# DRV8711_Breakout_Minimal.net
KiCad netlist of a schematic drawn in EAGLE
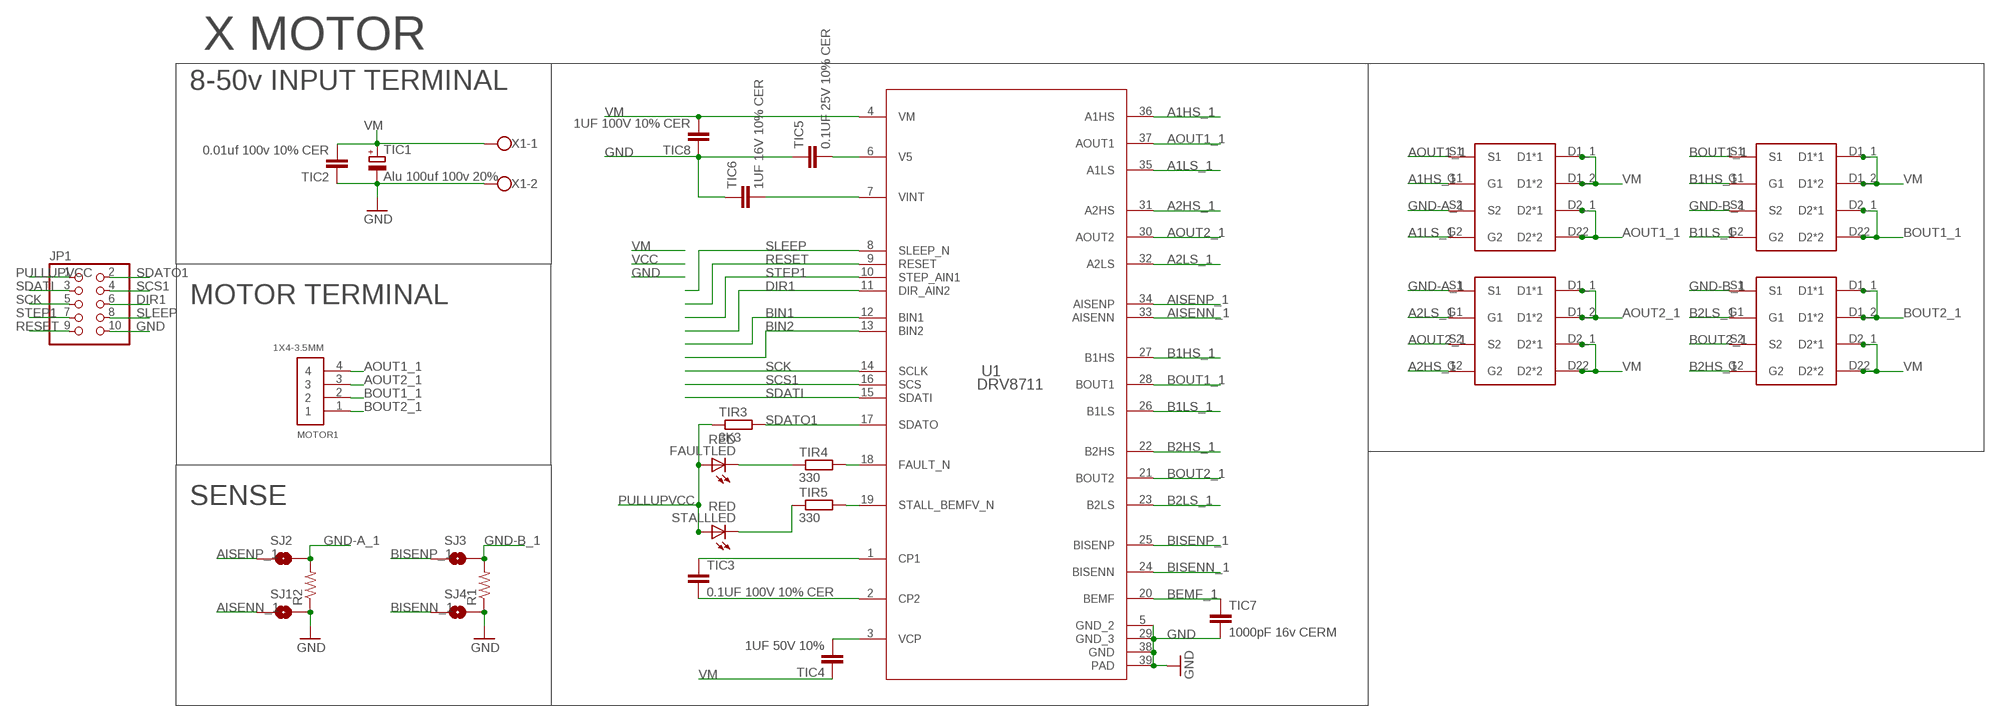
[diagram p0: schematic, sheet 1]

(export (version "E")
  (design (tool "Eeschema 10.0.6"))
  (components
    (comp (ref "FAULTLED")
      (value "RED")
      (footprint "eagle-import:1206")
      (libsource (lib "eagle-import") (part "LEDSMT1206"))
    )
    (comp (ref "JP1")
      (value "PINHD-2X5")
      (footprint "eagle-import:2X05")
      (libsource (lib "eagle-import") (part "PINHD-2X5"))
    )
    (comp (ref "MOTOR1")
      (value "1X4-3.5MM")
      (footprint "eagle-import:1X04-3.5MM")
      (libsource (lib "eagle-import") (part "1X4-3.5MM"))
    )
    (comp (ref "R1")
      (value "R-US_R2512")
      (footprint "eagle-import:R2512")
      (libsource (lib "eagle-import") (part "R-US_R2512"))
    )
    (comp (ref "R2")
      (value "R-US_R2512")
      (footprint "eagle-import:R2512")
      (libsource (lib "eagle-import") (part "R-US_R2512"))
    )
    (comp (ref "SJ1")
      (value "SOLDERJUMPERTRACE")
      (footprint "eagle-import:SJ_2S-TRACE")
      (libsource (lib "eagle-import") (part "SOLDERJUMPERTRACE"))
    )
    (comp (ref "SJ2")
      (value "SOLDERJUMPERTRACE")
      (footprint "eagle-import:SJ_2S-TRACE")
      (libsource (lib "eagle-import") (part "SOLDERJUMPERTRACE"))
    )
    (comp (ref "SJ3")
      (value "SOLDERJUMPERTRACE")
      (footprint "eagle-import:SJ_2S-TRACE")
      (libsource (lib "eagle-import") (part "SOLDERJUMPERTRACE"))
    )
    (comp (ref "SJ4")
      (value "SOLDERJUMPERTRACE")
      (footprint "eagle-import:SJ_2S-TRACE")
      (libsource (lib "eagle-import") (part "SOLDERJUMPERTRACE"))
    )
    (comp (ref "STALLLED")
      (value "RED")
      (footprint "eagle-import:1206")
      (libsource (lib "eagle-import") (part "LEDSMT1206"))
    )
    (comp (ref "TIC1")
      (value "Alu 100uf 100v 20%")
      (footprint "eagle-import:PANASONIC_E")
      (libsource (lib "eagle-import") (part "CPOL-EUE"))
    )
    (comp (ref "TIC2")
      (value "0.01uf 100v 10% CER")
      (footprint "eagle-import:C1206K")
      (libsource (lib "eagle-import") (part "C-EUC1206K"))
    )
    (comp (ref "TIC3")
      (value "0.1UF 100V 10% CER")
      (footprint "eagle-import:C1206K")
      (libsource (lib "eagle-import") (part "C-EUC1206K"))
    )
    (comp (ref "TIC4")
      (value "1UF 50V 10%")
      (footprint "eagle-import:C1206K")
      (libsource (lib "eagle-import") (part "C-EUC1206K"))
    )
    (comp (ref "TIC5")
      (value "0.1UF 25V 10% CER")
      (footprint "eagle-import:C1206K")
      (libsource (lib "eagle-import") (part "C-EUC1206K"))
    )
    (comp (ref "TIC6")
      (value "1UF 16V 10% CER")
      (footprint "eagle-import:C1206K")
      (libsource (lib "eagle-import") (part "C-EUC1206K"))
    )
    (comp (ref "TIC7")
      (value "1000pF 16v CERM")
      (footprint "eagle-import:C1206K")
      (libsource (lib "eagle-import") (part "C-EUC1206K"))
    )
    (comp (ref "TIC8")
      (value "1UF 100V 10% CER")
      (footprint "eagle-import:C1206K")
      (libsource (lib "eagle-import") (part "C-EUC1206K"))
    )
    (comp (ref "TIR3")
      (value "3K3")
      (footprint "eagle-import:R1206")
      (libsource (lib "eagle-import") (part "R-EU_R1206"))
    )
    (comp (ref "TIR4")
      (value "330")
      (footprint "eagle-import:R1206")
      (libsource (lib "eagle-import") (part "R-EU_R1206"))
    )
    (comp (ref "TIR5")
      (value "330")
      (footprint "eagle-import:R1206")
      (libsource (lib "eagle-import") (part "R-EU_R1206"))
    )
    (comp (ref "U$1")
      (value "CSD88537ND")
      (footprint "eagle-import:CSD88537ND")
      (libsource (lib "eagle-import") (part "CSD88537ND"))
    )
    (comp (ref "U$2")
      (value "CSD88537ND")
      (footprint "eagle-import:CSD88537ND")
      (libsource (lib "eagle-import") (part "CSD88537ND"))
    )
    (comp (ref "U$3")
      (value "CSD88537ND")
      (footprint "eagle-import:CSD88537ND")
      (libsource (lib "eagle-import") (part "CSD88537ND"))
    )
    (comp (ref "U$4")
      (value "CSD88537ND")
      (footprint "eagle-import:CSD88537ND")
      (libsource (lib "eagle-import") (part "CSD88537ND"))
    )
    (comp (ref "U1")
      (value "DRV8711")
      (footprint "eagle-import:DCP0038A_N")
      (fields
        (field (name "ALTERNATEPARTNUMBER") "DRV8711DCP")
        (field (name "MANUFACTURER") "Texas Instruments")
        (field (name "PARTNUMBER") "DRV8711DCPR")
      )
      (libsource (lib "eagle-import") (part "DRV8711DCPR"))
    )
    (comp (ref "X1")
      (value "W237-102")
      (footprint "eagle-import:W237-102")
      (fields (field (name "MPN") "237-102"))
      (libsource (lib "eagle-import") (part "W237-102"))
    )
  )
  (nets
    (net (code "1") (name "/A1HS_1") (class "Default")
      (node (ref "U$1") (pin "G1") (pinfunction "G1_G1") (pintype "power_in"))
      (node (ref "U1") (pin "36") (pinfunction "A1HS_36") (pintype "output"))
    )
    (net (code "2") (name "/A1LS_1") (class "Default")
      (node (ref "U$1") (pin "G2") (pinfunction "G2_G2") (pintype "power_in"))
      (node (ref "U1") (pin "35") (pinfunction "A1LS_35") (pintype "output"))
    )
    (net (code "3") (name "/A2HS_1") (class "Default")
      (node (ref "U$3") (pin "G2") (pinfunction "G2_G2") (pintype "power_in"))
      (node (ref "U1") (pin "31") (pinfunction "A2HS_31") (pintype "output"))
    )
    (net (code "4") (name "/A2LS_1") (class "Default")
      (node (ref "U$3") (pin "G1") (pinfunction "G1_G1") (pintype "power_in"))
      (node (ref "U1") (pin "32") (pinfunction "A2LS_32") (pintype "output"))
    )
    (net (code "5") (name "/AISENN_1") (class "Default")
      (node (ref "SJ1") (pin "1") (pinfunction "1_1") (pintype "passive"))
      (node (ref "U1") (pin "33") (pinfunction "AISENN_33") (pintype "input"))
    )
    (net (code "6") (name "/AISENP_1") (class "Default")
      (node (ref "SJ2") (pin "1") (pinfunction "1_1") (pintype "passive"))
      (node (ref "U1") (pin "34") (pinfunction "AISENP_34") (pintype "input"))
    )
    (net (code "7") (name "/AOUT1_1") (class "Default")
      (node (ref "MOTOR1") (pin "4") (pinfunction "4_4") (pintype "bidirectional"))
      (node (ref "U$1") (pin "D22") (pinfunction "D2*2_D22") (pintype "power_in"))
      (node (ref "U$1") (pin "D2_1") (pinfunction "D2*1_D2_1") (pintype "power_in"))
      (node (ref "U$1") (pin "S1") (pinfunction "S1_S1") (pintype "power_in"))
      (node (ref "U1") (pin "37") (pinfunction "AOUT1_37") (pintype "output"))
    )
    (net (code "8") (name "/AOUT2_1") (class "Default")
      (node (ref "MOTOR1") (pin "3") (pinfunction "3_3") (pintype "bidirectional"))
      (node (ref "U$3") (pin "D1_1") (pinfunction "D1*1_D1_1") (pintype "power_in"))
      (node (ref "U$3") (pin "D1_2") (pinfunction "D1*2_D1_2") (pintype "power_in"))
      (node (ref "U$3") (pin "S2") (pinfunction "S2_S2") (pintype "power_in"))
      (node (ref "U1") (pin "30") (pinfunction "AOUT2_30") (pintype "output"))
    )
    (net (code "9") (name "/B1HS_1") (class "Default")
      (node (ref "U$2") (pin "G1") (pinfunction "G1_G1") (pintype "power_in"))
      (node (ref "U1") (pin "27") (pinfunction "B1HS_27") (pintype "output"))
    )
    (net (code "10") (name "/B1LS_1") (class "Default")
      (node (ref "U$2") (pin "G2") (pinfunction "G2_G2") (pintype "power_in"))
      (node (ref "U1") (pin "26") (pinfunction "B1LS_26") (pintype "output"))
    )
    (net (code "11") (name "/B2HS_1") (class "Default")
      (node (ref "U$4") (pin "G2") (pinfunction "G2_G2") (pintype "power_in"))
      (node (ref "U1") (pin "22") (pinfunction "B2HS_22") (pintype "output"))
    )
    (net (code "12") (name "/B2LS_1") (class "Default")
      (node (ref "U$4") (pin "G1") (pinfunction "G1_G1") (pintype "power_in"))
      (node (ref "U1") (pin "23") (pinfunction "B2LS_23") (pintype "output"))
    )
    (net (code "13") (name "/BEMF_1") (class "Default")
      (node (ref "TIC7") (pin "1") (pinfunction "1_1") (pintype "passive"))
      (node (ref "U1") (pin "20") (pinfunction "BEMF_20") (pintype "output"))
    )
    (net (code "14") (name "/BIN1") (class "Default")
      (node (ref "U1") (pin "12") (pinfunction "BIN1_12") (pintype "input"))
    )
    (net (code "15") (name "/BIN2") (class "Default")
      (node (ref "U1") (pin "13") (pinfunction "BIN2_13") (pintype "input"))
    )
    (net (code "16") (name "/BISENN_1") (class "Default")
      (node (ref "SJ4") (pin "1") (pinfunction "1_1") (pintype "passive"))
      (node (ref "U1") (pin "24") (pinfunction "BISENN_24") (pintype "input"))
    )
    (net (code "17") (name "/BISENP_1") (class "Default")
      (node (ref "SJ3") (pin "1") (pinfunction "1_1") (pintype "passive"))
      (node (ref "U1") (pin "25") (pinfunction "BISENP_25") (pintype "input"))
    )
    (net (code "18") (name "/BOUT1_1") (class "Default")
      (node (ref "MOTOR1") (pin "2") (pinfunction "2_2") (pintype "bidirectional"))
      (node (ref "U$2") (pin "D22") (pinfunction "D2*2_D22") (pintype "power_in"))
      (node (ref "U$2") (pin "D2_1") (pinfunction "D2*1_D2_1") (pintype "power_in"))
      (node (ref "U$2") (pin "S1") (pinfunction "S1_S1") (pintype "power_in"))
      (node (ref "U1") (pin "28") (pinfunction "BOUT1_28") (pintype "output"))
    )
    (net (code "19") (name "/BOUT2_1") (class "Default")
      (node (ref "MOTOR1") (pin "1") (pinfunction "1_1") (pintype "bidirectional"))
      (node (ref "U$4") (pin "D1_1") (pinfunction "D1*1_D1_1") (pintype "power_in"))
      (node (ref "U$4") (pin "D1_2") (pinfunction "D1*2_D1_2") (pintype "power_in"))
      (node (ref "U$4") (pin "S2") (pinfunction "S2_S2") (pintype "power_in"))
      (node (ref "U1") (pin "21") (pinfunction "BOUT2_21") (pintype "output"))
    )
    (net (code "20") (name "/DIR1") (class "Default")
      (node (ref "JP1") (pin "6") (pinfunction "6_6") (pintype "passive"))
      (node (ref "U1") (pin "11") (pinfunction "DIR_AIN2_11") (pintype "input"))
    )
    (net (code "21") (name "/GND-A_1") (class "Default")
      (node (ref "R2") (pin "2") (pinfunction "2_2") (pintype "passive"))
      (node (ref "SJ2") (pin "2") (pinfunction "2_2") (pintype "passive"))
      (node (ref "U$1") (pin "S2") (pinfunction "S2_S2") (pintype "power_in"))
      (node (ref "U$3") (pin "S1") (pinfunction "S1_S1") (pintype "power_in"))
    )
    (net (code "22") (name "/GND-B_1") (class "Default")
      (node (ref "R1") (pin "2") (pinfunction "2_2") (pintype "passive"))
      (node (ref "SJ3") (pin "2") (pinfunction "2_2") (pintype "passive"))
      (node (ref "U$2") (pin "S2") (pinfunction "S2_S2") (pintype "power_in"))
      (node (ref "U$4") (pin "S1") (pinfunction "S1_S1") (pintype "power_in"))
    )
    (net (code "23") (name "/PULLUPVCC") (class "Default")
      (node (ref "FAULTLED") (pin "A") (pinfunction "A_A") (pintype "passive"))
      (node (ref "JP1") (pin "1") (pinfunction "1_1") (pintype "passive"))
      (node (ref "STALLLED") (pin "A") (pinfunction "A_A") (pintype "passive"))
      (node (ref "TIR3") (pin "1") (pinfunction "1_1") (pintype "passive"))
    )
    (net (code "24") (name "/RESET") (class "Default")
      (node (ref "JP1") (pin "9") (pinfunction "9_9") (pintype "passive"))
      (node (ref "U1") (pin "9") (pinfunction "RESET_9") (pintype "input"))
    )
    (net (code "25") (name "/SCK") (class "Default")
      (node (ref "JP1") (pin "5") (pinfunction "5_5") (pintype "passive"))
      (node (ref "U1") (pin "14") (pinfunction "SCLK_14") (pintype "input"))
    )
    (net (code "26") (name "/SCS1") (class "Default")
      (node (ref "JP1") (pin "4") (pinfunction "4_4") (pintype "passive"))
      (node (ref "U1") (pin "16") (pinfunction "SCS_16") (pintype "input"))
    )
    (net (code "27") (name "/SDATI") (class "Default")
      (node (ref "JP1") (pin "3") (pinfunction "3_3") (pintype "passive"))
      (node (ref "U1") (pin "15") (pinfunction "SDATI_15") (pintype "input"))
    )
    (net (code "28") (name "/SDATO1") (class "Default")
      (node (ref "JP1") (pin "2") (pinfunction "2_2") (pintype "passive"))
      (node (ref "TIR3") (pin "2") (pinfunction "2_2") (pintype "passive"))
      (node (ref "U1") (pin "17") (pinfunction "SDATO_17") (pintype "open_collector"))
    )
    (net (code "29") (name "/SLEEP") (class "Default")
      (node (ref "JP1") (pin "8") (pinfunction "8_8") (pintype "passive"))
      (node (ref "U1") (pin "8") (pinfunction "SLEEP_N_8") (pintype "input"))
    )
    (net (code "30") (name "/STEP1") (class "Default")
      (node (ref "JP1") (pin "7") (pinfunction "7_7") (pintype "passive"))
      (node (ref "U1") (pin "10") (pinfunction "STEP_AIN1_10") (pintype "input"))
    )
    (net (code "32") (name "/VM") (class "Default")
      (node (ref "TIC1") (pin "+") (pinfunction "+_+") (pintype "passive"))
      (node (ref "TIC2") (pin "2") (pinfunction "2_2") (pintype "passive"))
      (node (ref "TIC4") (pin "1") (pinfunction "1_1") (pintype "passive"))
      (node (ref "TIC8") (pin "2") (pinfunction "2_2") (pintype "passive"))
      (node (ref "U$1") (pin "D1_1") (pinfunction "D1*1_D1_1") (pintype "power_in"))
      (node (ref "U$1") (pin "D1_2") (pinfunction "D1*2_D1_2") (pintype "power_in"))
      (node (ref "U$2") (pin "D1_1") (pinfunction "D1*1_D1_1") (pintype "power_in"))
      (node (ref "U$2") (pin "D1_2") (pinfunction "D1*2_D1_2") (pintype "power_in"))
      (node (ref "U$3") (pin "D22") (pinfunction "D2*2_D22") (pintype "power_in"))
      (node (ref "U$3") (pin "D2_1") (pinfunction "D2*1_D2_1") (pintype "power_in"))
      (node (ref "U$4") (pin "D22") (pinfunction "D2*2_D22") (pintype "power_in"))
      (node (ref "U$4") (pin "D2_1") (pinfunction "D2*1_D2_1") (pintype "power_in"))
      (node (ref "U1") (pin "4") (pinfunction "VM_4") (pintype "power_in"))
      (node (ref "X1") (pin "1") (pinfunction "KL_1") (pintype "passive"))
    )
    (net (code "33") (name "GND") (class "Default")
      (node (ref "JP1") (pin "10") (pinfunction "10_10") (pintype "passive"))
      (node (ref "R1") (pin "1") (pinfunction "1_1") (pintype "passive"))
      (node (ref "R2") (pin "1") (pinfunction "1_1") (pintype "passive"))
      (node (ref "SJ1") (pin "2") (pinfunction "2_2") (pintype "passive"))
      (node (ref "SJ4") (pin "2") (pinfunction "2_2") (pintype "passive"))
      (node (ref "TIC1") (pin "-") (pinfunction "-_-") (pintype "passive"))
      (node (ref "TIC2") (pin "1") (pinfunction "1_1") (pintype "passive"))
      (node (ref "TIC5") (pin "1") (pinfunction "1_1") (pintype "passive"))
      (node (ref "TIC6") (pin "1") (pinfunction "1_1") (pintype "passive"))
      (node (ref "TIC7") (pin "2") (pinfunction "2_2") (pintype "passive"))
      (node (ref "TIC8") (pin "1") (pinfunction "1_1") (pintype "passive"))
      (node (ref "U1") (pin "29") (pinfunction "GND_3_29") (pintype "power_in"))
      (node (ref "U1") (pin "38") (pinfunction "GND_38") (pintype "power_in"))
      (node (ref "U1") (pin "39") (pinfunction "PAD_39") (pintype "power_in"))
      (node (ref "U1") (pin "5") (pinfunction "GND_2_5") (pintype "power_in"))
      (node (ref "X1") (pin "2") (pinfunction "KL_2") (pintype "passive"))
    )
    (net (code "34") (name "Net-(FAULTLED-PadC)") (class "Default")
      (node (ref "FAULTLED") (pin "C") (pinfunction "C_C") (pintype "passive"))
      (node (ref "TIR4") (pin "1") (pinfunction "1_1") (pintype "passive"))
    )
    (net (code "35") (name "Net-(STALLLED-PadC)") (class "Default")
      (node (ref "STALLLED") (pin "C") (pinfunction "C_C") (pintype "passive"))
      (node (ref "TIR5") (pin "1") (pinfunction "1_1") (pintype "passive"))
    )
    (net (code "36") (name "Net-(U1-CP1)") (class "Default")
      (node (ref "TIC3") (pin "1") (pinfunction "1_1") (pintype "passive"))
      (node (ref "U1") (pin "1") (pinfunction "CP1_1") (pintype "passive"))
    )
    (net (code "37") (name "Net-(U1-CP2)") (class "Default")
      (node (ref "TIC3") (pin "2") (pinfunction "2_2") (pintype "passive"))
      (node (ref "U1") (pin "2") (pinfunction "CP2_2") (pintype "passive"))
    )
    (net (code "38") (name "Net-(U1-FAULT_N)") (class "Default")
      (node (ref "TIR4") (pin "2") (pinfunction "2_2") (pintype "passive"))
      (node (ref "U1") (pin "18") (pinfunction "FAULT_N_18") (pintype "open_collector"))
    )
    (net (code "39") (name "Net-(U1-STALL_BEMFV_N)") (class "Default")
      (node (ref "TIR5") (pin "2") (pinfunction "2_2") (pintype "passive"))
      (node (ref "U1") (pin "19") (pinfunction "STALL_BEMFV_N_19") (pintype "open_collector"))
    )
    (net (code "40") (name "Net-(U1-V5)") (class "Default")
      (node (ref "TIC5") (pin "2") (pinfunction "2_2") (pintype "passive"))
      (node (ref "U1") (pin "6") (pinfunction "V5_6") (pintype "power_in"))
    )
    (net (code "41") (name "Net-(U1-VCP)") (class "Default")
      (node (ref "TIC4") (pin "2") (pinfunction "2_2") (pintype "passive"))
      (node (ref "U1") (pin "3") (pinfunction "VCP_3") (pintype "passive"))
    )
    (net (code "42") (name "Net-(U1-VINT)") (class "Default")
      (node (ref "TIC6") (pin "2") (pinfunction "2_2") (pintype "passive"))
      (node (ref "U1") (pin "7") (pinfunction "VINT_7") (pintype "power_in"))
    )
  )
)
